# FLASH.net
KiCad netlist of a schematic drawn in Altium Designer
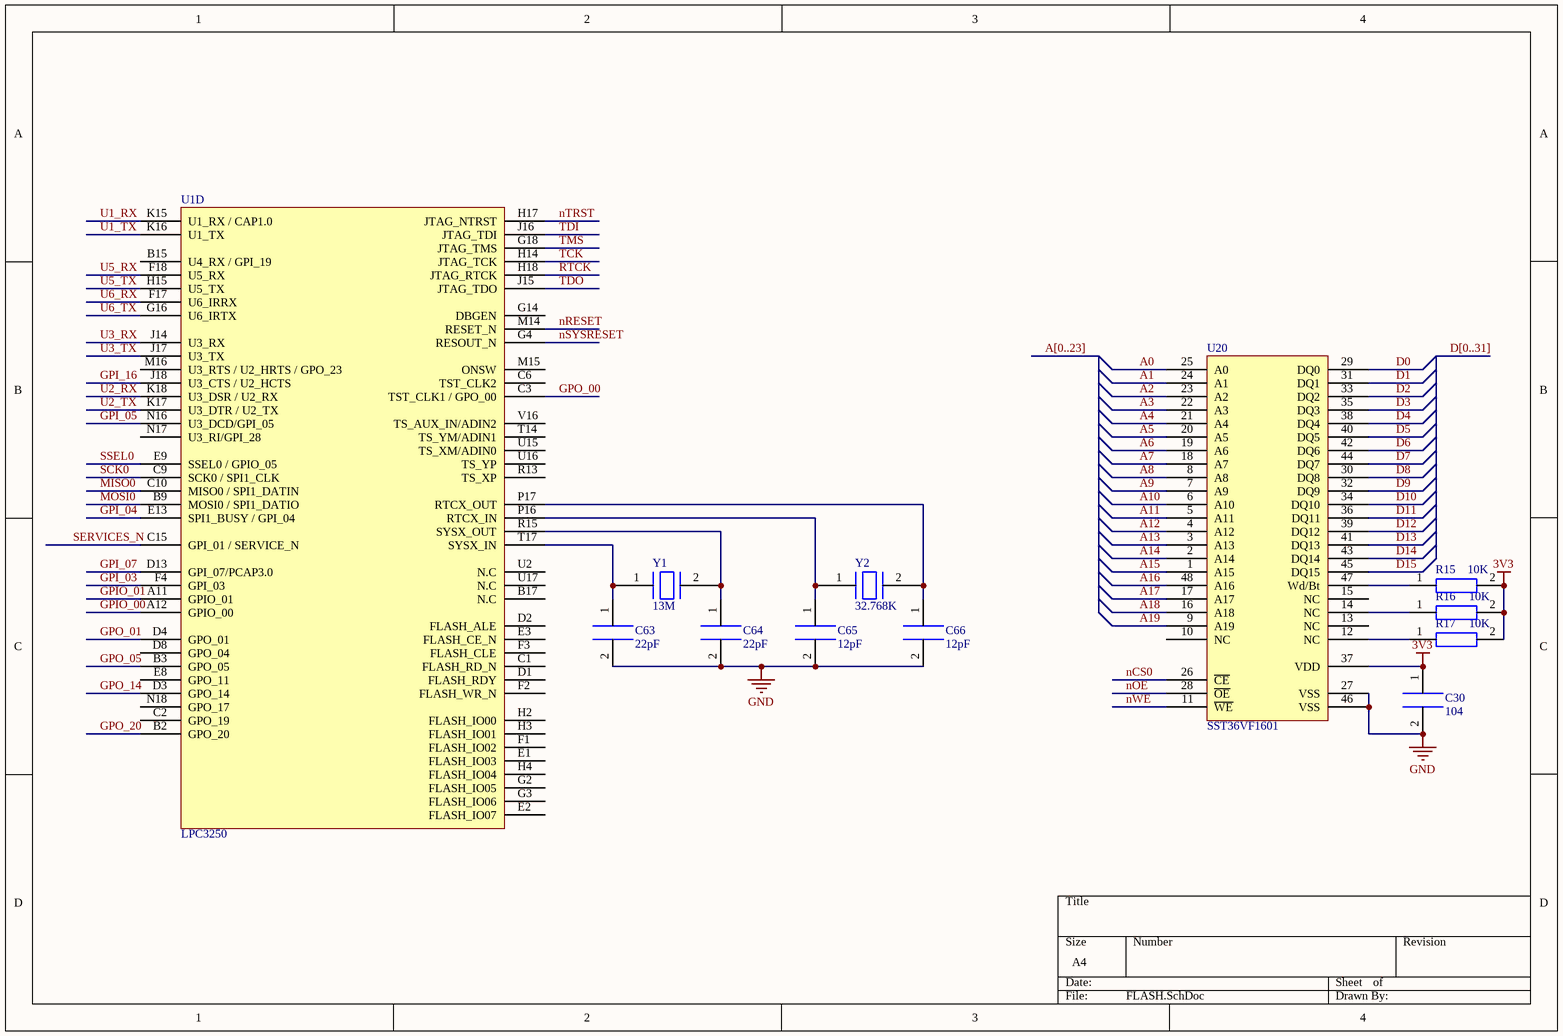
[diagram p0: FLASH.SchDoc]

(export (version "E")
  (design (tool "Eeschema 10.0.6"))
  (components
    (comp (ref "C30") (value "104") (footprint "0603C") (libsource (lib "MyProject1") (part "CAP")))
    (comp (ref "C63") (value "22pF") (footprint "0603C") (libsource (lib "MyProject1") (part "CAP")))
    (comp (ref "C64") (value "22pF") (footprint "0603C") (libsource (lib "MyProject1") (part "CAP")))
    (comp (ref "C65") (value "12pF") (footprint "0603C") (libsource (lib "MyProject1") (part "CAP")))
    (comp (ref "C66") (value "12pF") (footprint "0603C") (libsource (lib "MyProject1") (part "CAP")))
    (comp (ref "R15") (value "10K") (footprint "0603R") (libsource (lib "MyProject1") (part "RES")))
    (comp (ref "R16") (value "10K") (footprint "0603R") (libsource (lib "MyProject1") (part "RES")))
    (comp (ref "R17") (value "10K") (footprint "0603R") (libsource (lib "MyProject1") (part "RES")))
    (comp (ref "U1") (value "LPC3250") (footprint "TFBGA296") (libsource (lib "MyProject1") (part "LPC3250")))
    (comp (ref "U20")
      (value "SST36VF1601")
      (footprint "TSOP-48")
      (libsource (lib "MyProject1") (part "SST36VF1601"))
    )
    (comp (ref "Y1") (value "13M") (footprint "XTAL-D") (libsource (lib "MyProject1") (part "Y")))
    (comp (ref "Y2") (value "32.768K") (footprint "XTAL-D") (libsource (lib "MyProject1") (part "Y")))
  )
  (nets
    (net (code "21") (name "/A0") (class "Default")
      (node (ref "U20") (pin "25") (pinfunction "A0_25") (pintype "passive"))
    )
    (net (code "22") (name "/A1") (class "Default")
      (node (ref "U20") (pin "24") (pinfunction "A1_24") (pintype "passive"))
    )
    (net (code "23") (name "/A2") (class "Default")
      (node (ref "U20") (pin "23") (pinfunction "A2_23") (pintype "passive"))
    )
    (net (code "24") (name "/A3") (class "Default")
      (node (ref "U20") (pin "22") (pinfunction "A3_22") (pintype "passive"))
    )
    (net (code "25") (name "/A4") (class "Default")
      (node (ref "U20") (pin "21") (pinfunction "A4_21") (pintype "passive"))
    )
    (net (code "26") (name "/A5") (class "Default")
      (node (ref "U20") (pin "20") (pinfunction "A5_20") (pintype "passive"))
    )
    (net (code "27") (name "/A6") (class "Default")
      (node (ref "U20") (pin "19") (pinfunction "A6_19") (pintype "passive"))
    )
    (net (code "28") (name "/A7") (class "Default")
      (node (ref "U20") (pin "18") (pinfunction "A7_18") (pintype "passive"))
    )
    (net (code "29") (name "/A8") (class "Default")
      (node (ref "U20") (pin "8") (pinfunction "A8_8") (pintype "passive"))
    )
    (net (code "30") (name "/A9") (class "Default")
      (node (ref "U20") (pin "7") (pinfunction "A9_7") (pintype "passive"))
    )
    (net (code "31") (name "/A10") (class "Default")
      (node (ref "U20") (pin "6") (pinfunction "A10_6") (pintype "passive"))
    )
    (net (code "32") (name "/A11") (class "Default")
      (node (ref "U20") (pin "5") (pinfunction "A11_5") (pintype "passive"))
    )
    (net (code "33") (name "/A12") (class "Default")
      (node (ref "U20") (pin "4") (pinfunction "A12_4") (pintype "passive"))
    )
    (net (code "34") (name "/A13") (class "Default")
      (node (ref "U20") (pin "3") (pinfunction "A13_3") (pintype "passive"))
    )
    (net (code "35") (name "/A14") (class "Default")
      (node (ref "U20") (pin "2") (pinfunction "A14_2") (pintype "passive"))
    )
    (net (code "36") (name "/A15") (class "Default")
      (node (ref "U20") (pin "1") (pinfunction "A15_1") (pintype "passive"))
    )
    (net (code "37") (name "/A16") (class "Default")
      (node (ref "U20") (pin "48") (pinfunction "A16_48") (pintype "passive"))
    )
    (net (code "38") (name "/A17") (class "Default")
      (node (ref "U20") (pin "17") (pinfunction "A17_17") (pintype "passive"))
    )
    (net (code "39") (name "/A18") (class "Default")
      (node (ref "U20") (pin "16") (pinfunction "A18_16") (pintype "passive"))
    )
    (net (code "40") (name "/A19") (class "Default")
      (node (ref "U20") (pin "9") (pinfunction "A19_9") (pintype "passive"))
    )
    (net (code "42") (name "/D0") (class "Default")
      (node (ref "U20") (pin "29") (pinfunction "DQ0_29") (pintype "passive"))
    )
    (net (code "43") (name "/D1") (class "Default")
      (node (ref "U20") (pin "31") (pinfunction "DQ1_31") (pintype "passive"))
    )
    (net (code "44") (name "/D2") (class "Default")
      (node (ref "U20") (pin "33") (pinfunction "DQ2_33") (pintype "passive"))
    )
    (net (code "45") (name "/D3") (class "Default")
      (node (ref "U20") (pin "35") (pinfunction "DQ3_35") (pintype "passive"))
    )
    (net (code "46") (name "/D4") (class "Default")
      (node (ref "U20") (pin "38") (pinfunction "DQ4_38") (pintype "passive"))
    )
    (net (code "47") (name "/D5") (class "Default")
      (node (ref "U20") (pin "40") (pinfunction "DQ5_40") (pintype "passive"))
    )
    (net (code "48") (name "/D6") (class "Default")
      (node (ref "U20") (pin "42") (pinfunction "DQ6_42") (pintype "passive"))
    )
    (net (code "49") (name "/D7") (class "Default")
      (node (ref "U20") (pin "44") (pinfunction "DQ7_44") (pintype "passive"))
    )
    (net (code "50") (name "/D8") (class "Default")
      (node (ref "U20") (pin "30") (pinfunction "DQ8_30") (pintype "passive"))
    )
    (net (code "51") (name "/D9") (class "Default")
      (node (ref "U20") (pin "32") (pinfunction "DQ9_32") (pintype "passive"))
    )
    (net (code "52") (name "/D10") (class "Default")
      (node (ref "U20") (pin "34") (pinfunction "DQ10_34") (pintype "passive"))
    )
    (net (code "53") (name "/D11") (class "Default")
      (node (ref "U20") (pin "36") (pinfunction "DQ11_36") (pintype "passive"))
    )
    (net (code "54") (name "/D12") (class "Default")
      (node (ref "U20") (pin "39") (pinfunction "DQ12_39") (pintype "passive"))
    )
    (net (code "55") (name "/D13") (class "Default")
      (node (ref "U20") (pin "41") (pinfunction "DQ13_41") (pintype "passive"))
    )
    (net (code "56") (name "/D14") (class "Default")
      (node (ref "U20") (pin "43") (pinfunction "DQ14_43") (pintype "passive"))
    )
    (net (code "57") (name "/D15") (class "Default")
      (node (ref "U20") (pin "45") (pinfunction "DQ15_45") (pintype "passive"))
    )
    (net (code "59") (name "/GPIO_00") (class "Default")
      (node (ref "U1") (pin "A12") (pinfunction "GPIO_00_A12") (pintype "passive"))
    )
    (net (code "60") (name "/GPIO_01") (class "Default")
      (node (ref "U1") (pin "A11") (pinfunction "GPIO_01_A11") (pintype "passive"))
    )
    (net (code "61") (name "/GPI_03") (class "Default")
      (node (ref "U1") (pin "F4") (pinfunction "GPI_03_F4") (pintype "passive"))
    )
    (net (code "62") (name "/GPI_04") (class "Default")
      (node (ref "U1") (pin "E13") (pinfunction "SPI1_BUSY_/_GPI_04_E13") (pintype "passive"))
    )
    (net (code "63") (name "/GPI_05") (class "Default")
      (node (ref "U1") (pin "N16") (pinfunction "U3_DCD/GPI_05_N16") (pintype "passive"))
    )
    (net (code "64") (name "/GPI_07") (class "Default")
      (node (ref "U1") (pin "D13") (pinfunction "GPI_07/PCAP3.0_D13") (pintype "passive"))
    )
    (net (code "65") (name "/GPI_16") (class "Default")
      (node (ref "U1") (pin "J18") (pinfunction "U3_CTS_/_U2_HCTS_J18") (pintype "passive"))
    )
    (net (code "66") (name "/GPO_00") (class "Default")
      (node (ref "U1") (pin "C3") (pinfunction "TST_CLK1_/_GPO_00_C3") (pintype "passive"))
    )
    (net (code "67") (name "/GPO_01") (class "Default")
      (node (ref "U1") (pin "D4") (pinfunction "GPO_01_D4") (pintype "passive"))
    )
    (net (code "68") (name "/GPO_05") (class "Default")
      (node (ref "U1") (pin "B3") (pinfunction "GPO_05_B3") (pintype "passive"))
    )
    (net (code "69") (name "/GPO_14") (class "Default")
      (node (ref "U1") (pin "D3") (pinfunction "GPO_14_D3") (pintype "passive"))
    )
    (net (code "70") (name "/GPO_20") (class "Default")
      (node (ref "U1") (pin "B2") (pinfunction "GPO_20_B2") (pintype "passive"))
    )
    (net (code "71") (name "/MISO0") (class "Default")
      (node (ref "U1") (pin "C10") (pinfunction "MISO0_/_SPI1_DATIN_C10") (pintype "passive"))
    )
    (net (code "72") (name "/MOSI0") (class "Default")
      (node (ref "U1") (pin "B9") (pinfunction "MOSI0_/_SPI1_DATIO_B9") (pintype "passive"))
    )
    (net (code "73") (name "/RTCK") (class "Default")
      (node (ref "U1") (pin "H18") (pinfunction "JTAG_RTCK_H18") (pintype "passive"))
    )
    (net (code "74") (name "/SCK0") (class "Default")
      (node (ref "U1") (pin "C9") (pinfunction "SCK0_/_SPI1_CLK_C9") (pintype "passive"))
    )
    (net (code "75") (name "/SERVICES_N") (class "Default")
      (node (ref "U1") (pin "C15") (pinfunction "GPI_01_/_SERVICE_N_C15") (pintype "passive"))
    )
    (net (code "76") (name "/SSEL0") (class "Default")
      (node (ref "U1") (pin "E9") (pinfunction "SSEL0_/_GPIO_05_E9") (pintype "passive"))
    )
    (net (code "77") (name "/TCK") (class "Default")
      (node (ref "U1") (pin "H14") (pinfunction "JTAG_TCK_H14") (pintype "passive"))
    )
    (net (code "78") (name "/TDI") (class "Default")
      (node (ref "U1") (pin "J16") (pinfunction "JTAG_TDI_J16") (pintype "passive"))
    )
    (net (code "79") (name "/TDO") (class "Default")
      (node (ref "U1") (pin "J15") (pinfunction "JTAG_TDO_J15") (pintype "passive"))
    )
    (net (code "80") (name "/TMS") (class "Default")
      (node (ref "U1") (pin "G18") (pinfunction "JTAG_TMS_G18") (pintype "passive"))
    )
    (net (code "81") (name "/U1_RX") (class "Default")
      (node (ref "U1") (pin "K15") (pinfunction "U1_RX_/_CAP1.0_K15") (pintype "passive"))
    )
    (net (code "82") (name "/U1_TX") (class "Default")
      (node (ref "U1") (pin "K16") (pinfunction "U1_TX_K16") (pintype "passive"))
    )
    (net (code "83") (name "/U2_RX") (class "Default")
      (node (ref "U1") (pin "K18") (pinfunction "U3_DSR_/_U2_RX_K18") (pintype "passive"))
    )
    (net (code "84") (name "/U2_TX") (class "Default")
      (node (ref "U1") (pin "K17") (pinfunction "U3_DTR_/_U2_TX_K17") (pintype "passive"))
    )
    (net (code "85") (name "/U3_RX") (class "Default")
      (node (ref "U1") (pin "J14") (pinfunction "U3_RX_J14") (pintype "passive"))
    )
    (net (code "86") (name "/U3_TX") (class "Default")
      (node (ref "U1") (pin "J17") (pinfunction "U3_TX_J17") (pintype "passive"))
    )
    (net (code "87") (name "/U5_RX") (class "Default")
      (node (ref "U1") (pin "F18") (pinfunction "U5_RX_F18") (pintype "passive"))
    )
    (net (code "88") (name "/U5_TX") (class "Default")
      (node (ref "U1") (pin "H15") (pinfunction "U5_TX_H15") (pintype "passive"))
    )
    (net (code "89") (name "/U6_RX") (class "Default")
      (node (ref "U1") (pin "F17") (pinfunction "U6_IRRX_F17") (pintype "passive"))
    )
    (net (code "90") (name "/U6_TX") (class "Default")
      (node (ref "U1") (pin "G16") (pinfunction "U6_IRTX_G16") (pintype "passive"))
    )
    (net (code "91") (name "/nCS0") (class "Default")
      (node (ref "U20") (pin "26") (pinfunction "~{CE}_26") (pintype "passive"))
    )
    (net (code "92") (name "/nOE") (class "Default")
      (node (ref "U20") (pin "28") (pinfunction "~{OE}_28") (pintype "passive"))
    )
    (net (code "93") (name "/nRESET") (class "Default")
      (node (ref "U1") (pin "M14") (pinfunction "RESET_N_M14") (pintype "passive"))
    )
    (net (code "94") (name "/nSYSRESET") (class "Default")
      (node (ref "U1") (pin "G4") (pinfunction "RESOUT_N_G4") (pintype "passive"))
    )
    (net (code "95") (name "/nTRST") (class "Default")
      (node (ref "U1") (pin "H17") (pinfunction "JTAG_NTRST_H17") (pintype "passive"))
    )
    (net (code "96") (name "/nWE") (class "Default")
      (node (ref "U20") (pin "11") (pinfunction "~{WE}_11") (pintype "passive"))
    )
    (net (code "97") (name "3V3") (class "Default")
      (node (ref "C30") (pin "1") (pinfunction "1_1") (pintype "passive"))
      (node (ref "R15") (pin "2") (pinfunction "2_2") (pintype "passive"))
      (node (ref "R16") (pin "2") (pinfunction "2_2") (pintype "passive"))
      (node (ref "R17") (pin "2") (pinfunction "2_2") (pintype "passive"))
      (node (ref "U20") (pin "37") (pinfunction "VDD_37") (pintype "passive"))
    )
    (net (code "98") (name "GND") (class "Default")
      (node (ref "C30") (pin "2") (pinfunction "2_2") (pintype "passive"))
      (node (ref "C63") (pin "2") (pinfunction "2_2") (pintype "passive"))
      (node (ref "C64") (pin "2") (pinfunction "2_2") (pintype "passive"))
      (node (ref "C65") (pin "2") (pinfunction "2_2") (pintype "passive"))
      (node (ref "C66") (pin "2") (pinfunction "2_2") (pintype "passive"))
      (node (ref "U20") (pin "27") (pinfunction "VSS_27") (pintype "passive"))
      (node (ref "U20") (pin "46") (pinfunction "VSS_46") (pintype "passive"))
    )
    (net (code "99") (name "Net-(R16-Pad1)") (class "Default")
      (node (ref "R16") (pin "1") (pinfunction "1_1") (pintype "passive"))
      (node (ref "U20") (pin "14") (pinfunction "NC_14") (pintype "passive"))
    )
    (net (code "100") (name "Net-(R17-Pad1)") (class "Default")
      (node (ref "R17") (pin "1") (pinfunction "1_1") (pintype "passive"))
      (node (ref "U20") (pin "12") (pinfunction "NC_12") (pintype "passive"))
    )
    (net (code "101") (name "Net-(U1D-RTCX_IN)") (class "Default")
      (node (ref "C65") (pin "1") (pinfunction "1_1") (pintype "passive"))
      (node (ref "U1") (pin "P16") (pinfunction "RTCX_IN_P16") (pintype "passive"))
      (node (ref "Y2") (pin "1") (pinfunction "1_1") (pintype "passive"))
    )
    (net (code "102") (name "Net-(U1D-RTCX_OUT)") (class "Default")
      (node (ref "C66") (pin "1") (pinfunction "1_1") (pintype "passive"))
      (node (ref "U1") (pin "P17") (pinfunction "RTCX_OUT_P17") (pintype "passive"))
      (node (ref "Y2") (pin "2") (pinfunction "2_2") (pintype "passive"))
    )
    (net (code "103") (name "Net-(U1D-SYSX_IN)") (class "Default")
      (node (ref "C63") (pin "1") (pinfunction "1_1") (pintype "passive"))
      (node (ref "U1") (pin "T17") (pinfunction "SYSX_IN_T17") (pintype "passive"))
      (node (ref "Y1") (pin "1") (pinfunction "1_1") (pintype "passive"))
    )
    (net (code "104") (name "Net-(U1D-SYSX_OUT)") (class "Default")
      (node (ref "C64") (pin "1") (pinfunction "1_1") (pintype "passive"))
      (node (ref "U1") (pin "R15") (pinfunction "SYSX_OUT_R15") (pintype "passive"))
      (node (ref "Y1") (pin "2") (pinfunction "2_2") (pintype "passive"))
    )
    (net (code "105") (name "Net-(U20-Wd{slash}Bt)") (class "Default")
      (node (ref "R15") (pin "1") (pinfunction "1_1") (pintype "passive"))
      (node (ref "U20") (pin "47") (pinfunction "Wd/Bt_47") (pintype "passive"))
    )
    (net (code "106") (name "unconnected-(U1D-DBGEN-PadG14)") (class "Default")
      (node (ref "U1") (pin "G14") (pinfunction "DBGEN_G14") (pintype "passive"))
    )
    (net (code "107") (name "unconnected-(U1D-FLASH_ALE-PadD2)") (class "Default")
      (node (ref "U1") (pin "D2") (pinfunction "FLASH_ALE_D2") (pintype "passive"))
    )
    (net (code "108") (name "unconnected-(U1D-FLASH_CE_N-PadE3)") (class "Default")
      (node (ref "U1") (pin "E3") (pinfunction "FLASH_CE_N_E3") (pintype "passive"))
    )
    (net (code "109") (name "unconnected-(U1D-FLASH_CLE-PadF3)") (class "Default")
      (node (ref "U1") (pin "F3") (pinfunction "FLASH_CLE_F3") (pintype "passive"))
    )
    (net (code "110") (name "unconnected-(U1D-FLASH_IO00-PadH2)") (class "Default")
      (node (ref "U1") (pin "H2") (pinfunction "FLASH_IO00_H2") (pintype "passive"))
    )
    (net (code "111") (name "unconnected-(U1D-FLASH_IO01-PadH3)") (class "Default")
      (node (ref "U1") (pin "H3") (pinfunction "FLASH_IO01_H3") (pintype "passive"))
    )
    (net (code "112") (name "unconnected-(U1D-FLASH_IO02-PadF1)") (class "Default")
      (node (ref "U1") (pin "F1") (pinfunction "FLASH_IO02_F1") (pintype "passive"))
    )
    (net (code "113") (name "unconnected-(U1D-FLASH_IO03-PadE1)") (class "Default")
      (node (ref "U1") (pin "E1") (pinfunction "FLASH_IO03_E1") (pintype "passive"))
    )
    (net (code "114") (name "unconnected-(U1D-FLASH_IO04-PadH4)") (class "Default")
      (node (ref "U1") (pin "H4") (pinfunction "FLASH_IO04_H4") (pintype "passive"))
    )
    (net (code "115") (name "unconnected-(U1D-FLASH_IO05-PadG2)") (class "Default")
      (node (ref "U1") (pin "G2") (pinfunction "FLASH_IO05_G2") (pintype "passive"))
    )
    (net (code "116") (name "unconnected-(U1D-FLASH_IO06-PadG3)") (class "Default")
      (node (ref "U1") (pin "G3") (pinfunction "FLASH_IO06_G3") (pintype "passive"))
    )
    (net (code "117") (name "unconnected-(U1D-FLASH_IO07-PadE2)") (class "Default")
      (node (ref "U1") (pin "E2") (pinfunction "FLASH_IO07_E2") (pintype "passive"))
    )
    (net (code "118") (name "unconnected-(U1D-FLASH_RDY-PadD1)") (class "Default")
      (node (ref "U1") (pin "D1") (pinfunction "FLASH_RDY_D1") (pintype "passive"))
    )
    (net (code "119") (name "unconnected-(U1D-FLASH_RD_N-PadC1)") (class "Default")
      (node (ref "U1") (pin "C1") (pinfunction "FLASH_RD_N_C1") (pintype "passive"))
    )
    (net (code "120") (name "unconnected-(U1D-FLASH_WR_N-PadF2)") (class "Default")
      (node (ref "U1") (pin "F2") (pinfunction "FLASH_WR_N_F2") (pintype "passive"))
    )
    (net (code "121") (name "unconnected-(U1D-GPO_04-PadD8)") (class "Default")
      (node (ref "U1") (pin "D8") (pinfunction "GPO_04_D8") (pintype "passive"))
    )
    (net (code "122") (name "unconnected-(U1D-GPO_11-PadE8)") (class "Default")
      (node (ref "U1") (pin "E8") (pinfunction "GPO_11_E8") (pintype "passive"))
    )
    (net (code "123") (name "unconnected-(U1D-GPO_17-PadN18)") (class "Default")
      (node (ref "U1") (pin "N18") (pinfunction "GPO_17_N18") (pintype "passive"))
    )
    (net (code "124") (name "unconnected-(U1D-GPO_19-PadC2)") (class "Default")
      (node (ref "U1") (pin "C2") (pinfunction "GPO_19_C2") (pintype "passive"))
    )
    (net (code "125") (name "unconnected-(U1D-N.C-PadB17)") (class "Default")
      (node (ref "U1") (pin "B17") (pinfunction "N.C_B17") (pintype "passive"))
    )
    (net (code "126") (name "unconnected-(U1D-N.C-PadU2)") (class "Default")
      (node (ref "U1") (pin "U2") (pinfunction "N.C_U2") (pintype "passive"))
    )
    (net (code "127") (name "unconnected-(U1D-N.C-PadU17)") (class "Default")
      (node (ref "U1") (pin "U17") (pinfunction "N.C_U17") (pintype "passive"))
    )
    (net (code "128") (name "unconnected-(U1D-ONSW-PadM15)") (class "Default")
      (node (ref "U1") (pin "M15") (pinfunction "ONSW_M15") (pintype "passive"))
    )
    (net (code "129") (name "unconnected-(U1D-TST_CLK2-PadC6)") (class "Default")
      (node (ref "U1") (pin "C6") (pinfunction "TST_CLK2_C6") (pintype "passive"))
    )
    (net (code "130") (name "unconnected-(U1D-TS_AUX_IN{slash}ADIN2-PadV16)") (class "Default")
      (node (ref "U1") (pin "V16") (pinfunction "TS_AUX_IN/ADIN2_V16") (pintype "passive"))
    )
    (net (code "131") (name "unconnected-(U1D-TS_XM{slash}ADIN0-PadU15)") (class "Default")
      (node (ref "U1") (pin "U15") (pinfunction "TS_XM/ADIN0_U15") (pintype "passive"))
    )
    (net (code "132") (name "unconnected-(U1D-TS_XP-PadR13)") (class "Default")
      (node (ref "U1") (pin "R13") (pinfunction "TS_XP_R13") (pintype "passive"))
    )
    (net (code "133") (name "unconnected-(U1D-TS_YM{slash}ADIN1-PadT14)") (class "Default")
      (node (ref "U1") (pin "T14") (pinfunction "TS_YM/ADIN1_T14") (pintype "passive"))
    )
    (net (code "134") (name "unconnected-(U1D-TS_YP-PadU16)") (class "Default")
      (node (ref "U1") (pin "U16") (pinfunction "TS_YP_U16") (pintype "passive"))
    )
    (net (code "135") (name "unconnected-(U1D-U3_RI{slash}GPI_28-PadN17)") (class "Default")
      (node (ref "U1") (pin "N17") (pinfunction "U3_RI/GPI_28_N17") (pintype "passive"))
    )
    (net (code "136") (name "unconnected-(U1D-U3_RTS_{slash}_U2_HRTS_{slash}_GPO_23-PadM16)") (class "Default")
      (node (ref "U1") (pin "M16") (pinfunction "U3_RTS_/_U2_HRTS_/_GPO_23_M16") (pintype "passive"))
    )
    (net (code "137") (name "unconnected-(U1D-U4_RX_{slash}_GPI_19-PadB15)") (class "Default")
      (node (ref "U1") (pin "B15") (pinfunction "U4_RX_/_GPI_19_B15") (pintype "passive"))
    )
    (net (code "138") (name "unconnected-(U20-NC-Pad10)") (class "Default")
      (node (ref "U20") (pin "10") (pinfunction "NC_10") (pintype "passive"))
    )
    (net (code "139") (name "unconnected-(U20-NC-Pad13)") (class "Default")
      (node (ref "U20") (pin "13") (pinfunction "NC_13") (pintype "passive"))
    )
    (net (code "140") (name "unconnected-(U20-NC-Pad15)") (class "Default")
      (node (ref "U20") (pin "15") (pinfunction "NC_15") (pintype "passive"))
    )
  )
)
